# Motor_Driver.net
KiCad netlist of a schematic drawn in Altium Designer
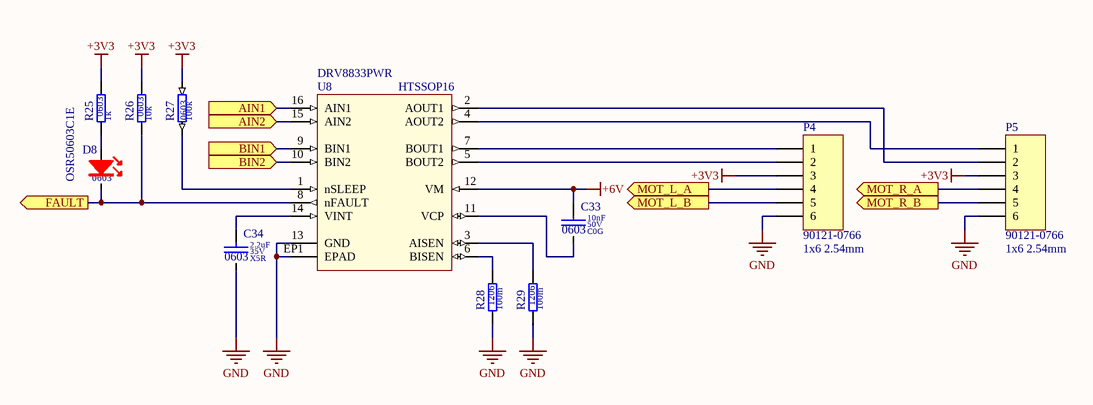
[diagram p0: Motor Driver.SchDoc]

(export (version "E")
  (design (tool "Eeschema 10.0.6"))
  (components
    (comp (ref "C33")
      (value "10nF")
      (footprint "C_0603_1608")
      (description "Capacitor")
      (fields
        (field (name "DIELECTRIC") "C0G")
        (field (name "VOLTAGE") "50V")
        (field (name "SCH_FOOTPRINT") "0603")
        (field (name "PART NUMBER") "C_10nF_50V_C0G_0603_5")
        (field (name "MANUFACTURER") "Murata")
      )
      (libsource (lib "Library") (part "C"))
    )
    (comp (ref "C34")
      (value "2.2uF")
      (footprint "C_0603_1608")
      (description "Capacitor")
      (fields
        (field (name "DIELECTRIC") "X5R")
        (field (name "VOLTAGE") "35V")
        (field (name "SCH_FOOTPRINT") "0603")
        (field (name "PART NUMBER") "C_2.2uF_35V_X5R_0603_10")
        (field (name "MANUFACTURER") "Murata")
      )
      (libsource (lib "Library") (part "C"))
    )
    (comp (ref "D8")
      (value "OSR50603C1E")
      (footprint "OL_0603_1608")
      (description "LED_RED")
      (fields
        (field (name "SCH_FOOTPRINT") "0603")
        (field (name "PART NUMBER") "OL_R_0603_OSR50603C1E")
        (field (name "MANUFACTURER") "Optosupply")
      )
      (libsource (lib "Library") (part "OL_R"))
    )
    (comp (ref "P4")
      (value "90121-0766")
      (footprint "P_HEADER_1x6_2.54_ANGLE")
      (description "Header, 6-Pin")
      (fields
        (field (name "PART NUMBER") "P_HEADER_1x6_2.54_ANGLE")
        (field (name "SCH_FOOTPRINT") "1x6 2.54mm")
        (field (name "MANUFACTURER") "Molex")
      )
      (libsource (lib "Library") (part "P_HEADER_1x6"))
    )
    (comp (ref "P5")
      (value "90121-0766")
      (footprint "P_HEADER_1x6_2.54_ANGLE")
      (description "Header, 6-Pin")
      (fields
        (field (name "PART NUMBER") "P_HEADER_1x6_2.54_ANGLE")
        (field (name "SCH_FOOTPRINT") "1x6 2.54mm")
        (field (name "MANUFACTURER") "Molex")
      )
      (libsource (lib "Library") (part "P_HEADER_1x6"))
    )
    (comp (ref "R25")
      (value "1k")
      (footprint "R_0603_1608")
      (fields
        (field (name "SCH_FOOTPRINT") "0603")
        (field (name "PART NUMBER") "R_1k_0603_1")
        (field (name "VOLTAGE") "75V")
        (field (name "POWER") "100mW")
      )
      (libsource (lib "Library") (part "R"))
    )
    (comp (ref "R26")
      (value "10k")
      (footprint "R_0603_1608")
      (fields
        (field (name "SCH_FOOTPRINT") "0603")
        (field (name "PART NUMBER") "R_10k_0603_1")
        (field (name "VOLTAGE") "75V")
        (field (name "POWER") "100mW")
      )
      (libsource (lib "Library") (part "R"))
    )
    (comp (ref "R27")
      (value "100k")
      (footprint "R_0603_1608")
      (fields
        (field (name "SCH_FOOTPRINT") "0603")
        (field (name "PART NUMBER") "R_100k_0603_1")
        (field (name "VOLTAGE") "50V")
        (field (name "POWER") "100mW")
      )
      (libsource (lib "") (part "R_1"))
    )
    (comp (ref "R28")
      (value "100m")
      (footprint "R_1206_3216")
      (fields
        (field (name "SCH_FOOTPRINT") "1206")
        (field (name "PART NUMBER") "R_100m_1206_1")
        (field (name "VOLTAGE") "316mV")
        (field (name "POWER") "1W")
      )
      (libsource (lib "Library") (part "R"))
    )
    (comp (ref "R29")
      (value "100m")
      (footprint "R_1206_3216")
      (fields
        (field (name "SCH_FOOTPRINT") "1206")
        (field (name "PART NUMBER") "R_100m_1206_1")
        (field (name "VOLTAGE") "316mV")
        (field (name "POWER") "1W")
      )
      (libsource (lib "Library") (part "R"))
    )
    (comp (ref "U8")
      (value "DRV8833PWR")
      (footprint "HTSSOP16_45x66x20_M")
      (fields
        (field (name "SCH_FOOTPRINT") "HTSSOP16")
        (field (name "PART NUMBER") "U_DRV8833PWR")
        (field (name "MANUFACTURER") "Texas Instruments")
        (field (name "Comment") "2A Low Voltage Dual Brushed DC or Single Bipolar Stepper Motor Driver (PWM Ctrl)")
      )
      (libsource (lib "Library") (part "U_DRV8833_HTSSOP_TSSOP"))
    )
  )
  (nets
    (net (code "1") (name "+3V3") (class "Default")
      (node (ref "P4") (pin "3") (pinfunction "3_3") (pintype "passive"))
      (node (ref "P5") (pin "3") (pinfunction "3_3") (pintype "passive"))
      (node (ref "R25") (pin "2") (pinfunction "2_2") (pintype "passive"))
      (node (ref "R26") (pin "2") (pinfunction "2_2") (pintype "passive"))
      (node (ref "R27") (pin "1") (pinfunction "1_1") (pintype "input"))
    )
    (net (code "2") (name "+6V") (class "Default")
      (node (ref "C33") (pin "1") (pinfunction "1_1") (pintype "passive"))
      (node (ref "U8") (pin "12") (pinfunction "VM_12") (pintype "input"))
    )
    (net (code "3") (name "/AIN1") (class "Default")
      (node (ref "U8") (pin "16") (pinfunction "AIN1_16") (pintype "input"))
    )
    (net (code "4") (name "/AIN2") (class "Default")
      (node (ref "U8") (pin "15") (pinfunction "AIN2_15") (pintype "input"))
    )
    (net (code "5") (name "/BIN1") (class "Default")
      (node (ref "U8") (pin "9") (pinfunction "BIN1_9") (pintype "input"))
    )
    (net (code "6") (name "/BIN2") (class "Default")
      (node (ref "U8") (pin "10") (pinfunction "BIN2_10") (pintype "input"))
    )
    (net (code "7") (name "/FAULT") (class "Default")
      (node (ref "D8") (pin "1") (pinfunction "K_1") (pintype "passive"))
      (node (ref "R26") (pin "1") (pinfunction "1_1") (pintype "passive"))
      (node (ref "U8") (pin "8") (pinfunction "nFAULT_8") (pintype "output"))
    )
    (net (code "8") (name "/MOT_L_A") (class "Default")
      (node (ref "P4") (pin "4") (pinfunction "4_4") (pintype "passive"))
    )
    (net (code "9") (name "/MOT_L_B") (class "Default")
      (node (ref "P4") (pin "5") (pinfunction "5_5") (pintype "passive"))
    )
    (net (code "10") (name "/MOT_R_A") (class "Default")
      (node (ref "P5") (pin "4") (pinfunction "4_4") (pintype "passive"))
    )
    (net (code "11") (name "/MOT_R_B") (class "Default")
      (node (ref "P5") (pin "5") (pinfunction "5_5") (pintype "passive"))
    )
    (net (code "12") (name "GND") (class "Default")
      (node (ref "C34") (pin "2") (pinfunction "2_2") (pintype "passive"))
      (node (ref "P4") (pin "6") (pinfunction "6_6") (pintype "passive"))
      (node (ref "P5") (pin "6") (pinfunction "6_6") (pintype "passive"))
      (node (ref "R28") (pin "1") (pinfunction "1_1") (pintype "passive"))
      (node (ref "R29") (pin "1") (pinfunction "1_1") (pintype "passive"))
      (node (ref "U8") (pin "13") (pinfunction "GND_13") (pintype "power_in"))
      (node (ref "U8") (pin "EP1") (pinfunction "EPAD_EP1") (pintype "power_in"))
    )
    (net (code "13") (name "Net-(D8-A)") (class "Default")
      (node (ref "D8") (pin "2") (pinfunction "A_2") (pintype "passive"))
      (node (ref "R25") (pin "1") (pinfunction "1_1") (pintype "passive"))
    )
    (net (code "14") (name "Net-(U8-AISEN)") (class "Default")
      (node (ref "R29") (pin "2") (pinfunction "2_2") (pintype "passive"))
      (node (ref "U8") (pin "3") (pinfunction "AISEN_3") (pintype "bidirectional"))
    )
    (net (code "15") (name "Net-(U8-AOUT1)") (class "Default")
      (node (ref "P5") (pin "2") (pinfunction "2_2") (pintype "passive"))
      (node (ref "U8") (pin "2") (pinfunction "AOUT1_2") (pintype "output"))
    )
    (net (code "16") (name "Net-(U8-AOUT2)") (class "Default")
      (node (ref "P5") (pin "1") (pinfunction "1_1") (pintype "passive"))
      (node (ref "U8") (pin "4") (pinfunction "AOUT2_4") (pintype "output"))
    )
    (net (code "17") (name "Net-(U8-BISEN)") (class "Default")
      (node (ref "R28") (pin "2") (pinfunction "2_2") (pintype "passive"))
      (node (ref "U8") (pin "6") (pinfunction "BISEN_6") (pintype "bidirectional"))
    )
    (net (code "18") (name "Net-(U8-BOUT1)") (class "Default")
      (node (ref "P4") (pin "1") (pinfunction "1_1") (pintype "passive"))
      (node (ref "U8") (pin "7") (pinfunction "BOUT1_7") (pintype "output"))
    )
    (net (code "19") (name "Net-(U8-BOUT2)") (class "Default")
      (node (ref "P4") (pin "2") (pinfunction "2_2") (pintype "passive"))
      (node (ref "U8") (pin "5") (pinfunction "BOUT2_5") (pintype "output"))
    )
    (net (code "20") (name "Net-(U8-VCP)") (class "Default")
      (node (ref "C33") (pin "2") (pinfunction "2_2") (pintype "passive"))
      (node (ref "U8") (pin "11") (pinfunction "VCP_11") (pintype "bidirectional"))
    )
    (net (code "21") (name "Net-(U8-VINT)") (class "Default")
      (node (ref "C34") (pin "1") (pinfunction "1_1") (pintype "passive"))
      (node (ref "U8") (pin "14") (pinfunction "VINT_14") (pintype "input"))
    )
    (net (code "22") (name "Net-(U8-nSLEEP)") (class "Default")
      (node (ref "R27") (pin "2") (pinfunction "2_2") (pintype "output"))
      (node (ref "U8") (pin "1") (pinfunction "nSLEEP_1") (pintype "input"))
    )
  )
)
